# SD_Card.net
KiCad netlist of a schematic drawn in Altium Designer
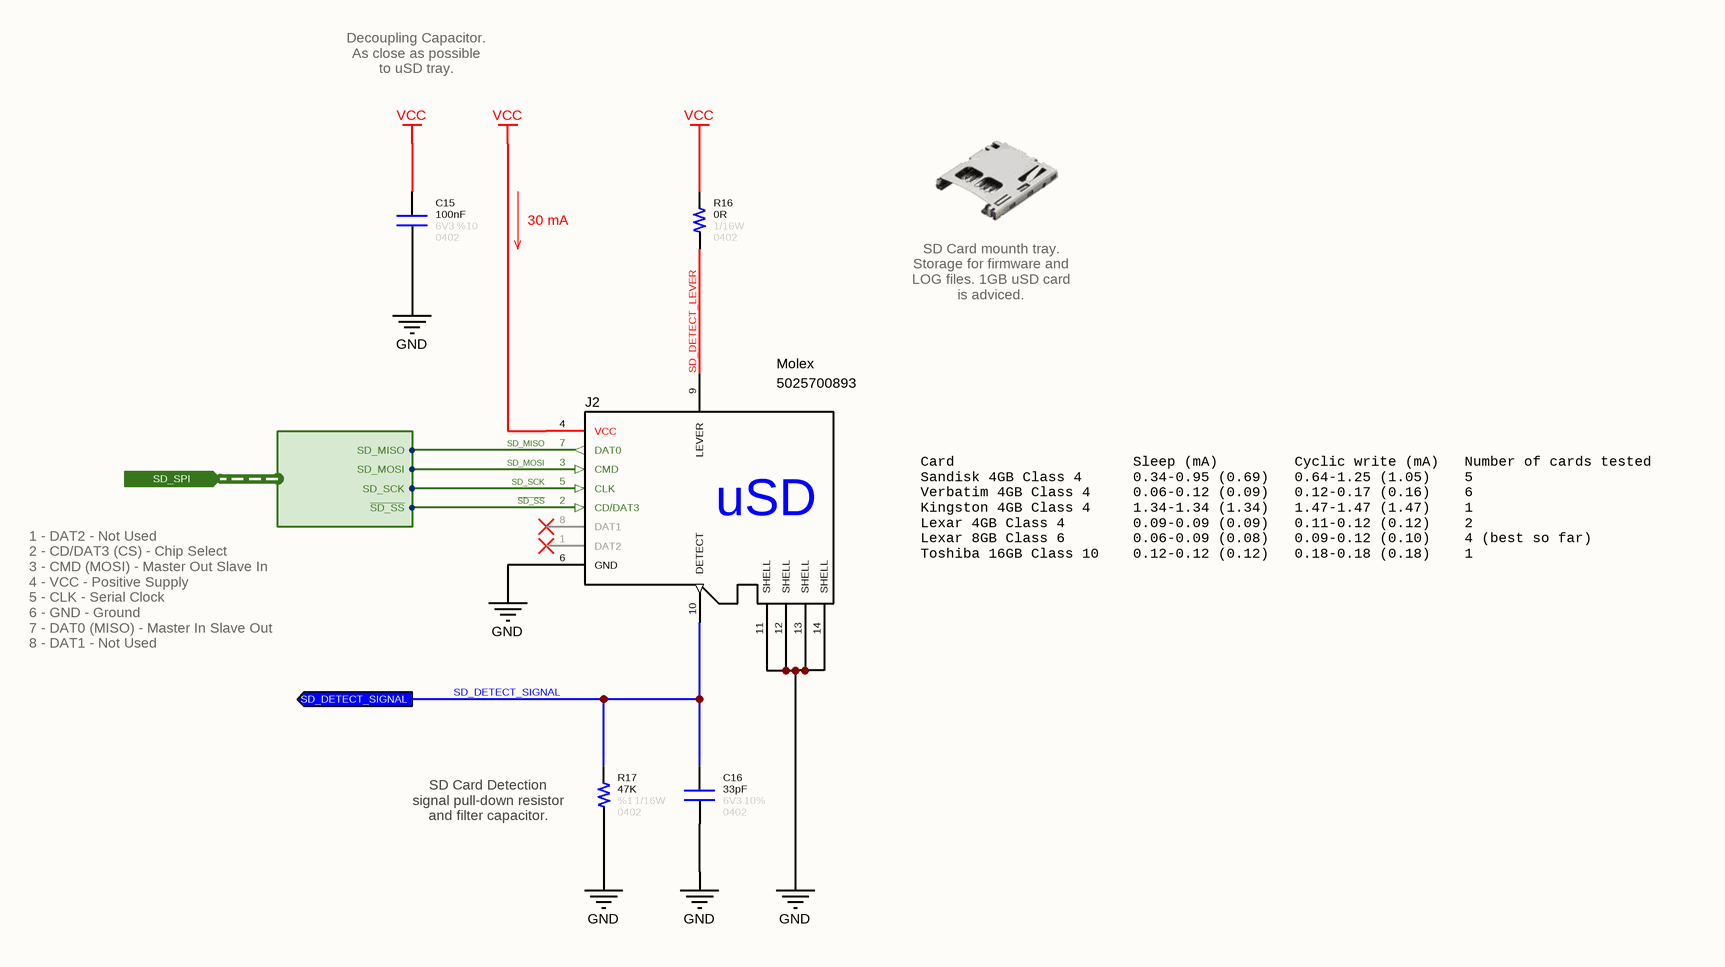
[diagram p0: SD Card.SchDoc]

(export (version "E")
  (design (tool "Eeschema 10.0.6"))
  (components
    (comp (ref "C15")
      (value "100nF")
      (footprint "CAPACITOR_0402")
      (description "Capacitor - 100nF [0402-6V3] (Ceramic)")
      (fields
        (field (name "MANUFACTURER PART NUMBER") "04026D104KAT4A")
        (field (name "TOLERANCE") "%10")
        (field (name "VOLTAGE") "6V3")
        (field (name "CASE") "0402")
        (field (name "Comment") "Capacitor - 100nF [0402] (Ceramic)")
      )
      (libsource (lib "P101DA_Library") (part "Capacitor - 100nF [0402-6V3]"))
    )
    (comp (ref "C16")
      (value "33pF")
      (footprint "CAPACITOR_0402")
      (description "Capacitor - 33pF [0402] (Ceramic)")
      (fields
        (field (name "MANUFACTURER PART NUMBER") "C0402C330J9RACAUTO")
        (field (name "TOLERANCE") "10%")
        (field (name "CASE") "0402")
        (field (name "VOLTAGE") "6V3")
      )
      (libsource (lib "P101DA_Library") (part "Capacitor - 33pF [0402-6V3]"))
    )
    (comp (ref "J2")
      (value "5025700893")
      (footprint "CONNECTOR - SD Card")
      (description "CONN MICRO SD CARD PUSH-PUSH R/A")
      (fields
        (field (name "MANUFACTURER NAME") "Molex")
        (field (name "MANUFACTURER PART NUMBER") "5025700893")
      )
      (libsource (lib "P101DA_Library") (part "Connector - SD Card Slot"))
    )
    (comp (ref "R16")
      (value "0R")
      (footprint "RESISTOR_0402")
      (description "Thick Film Resistors - SMD 1/16 W 0 Ohm")
      (fields
        (field (name "MANUFACTURER PART NUMBER") "CRCW04020000Z0ED")
        (field (name "CASE") "0402")
        (field (name "POWER") "1/16W")
        (field (name "Comment") "0R - 0402 - %1 - 1/16W")
      )
      (libsource (lib "P101DA_Library") (part "Resistor - 0R [0402]"))
    )
    (comp (ref "R17")
      (value "47K")
      (footprint "RESISTOR_0402")
      (description "Thick Film Resistors - SMD 1/16 W 47 KOhm 1%")
      (fields
        (field (name "MANUFACTURER PART NUMBER") "CRCW040247K0FKED")
        (field (name "TOLERANCE") "%1")
        (field (name "CASE") "0402")
        (field (name "POWER") "1/16W")
        (field (name "Comment") "47K - 0402 - %1 - 1/16W")
      )
      (libsource (lib "P101DA_Library") (part "Resistor - 47K [0402]"))
    )
  )
  (nets
    (net (code "2") (name "/SD_DETECT_LEVER") (class "Default")
      (node (ref "J2") (pin "9") (pinfunction "LEVER_9") (pintype "power_in"))
      (node (ref "R16") (pin "1") (pinfunction "1_1") (pintype "passive"))
    )
    (net (code "3") (name "/SD_DETECT_SIGNAL") (class "Default")
      (node (ref "C16") (pin "2") (pinfunction "2_2") (pintype "passive"))
      (node (ref "J2") (pin "10") (pinfunction "DETECT_10") (pintype "output"))
      (node (ref "R17") (pin "2") (pinfunction "2_2") (pintype "passive"))
    )
    (net (code "4") (name "/SD_MISO") (class "Default")
      (node (ref "J2") (pin "7") (pinfunction "DAT0_7") (pintype "output"))
    )
    (net (code "5") (name "/SD_MOSI") (class "Default")
      (node (ref "J2") (pin "3") (pinfunction "CMD_3") (pintype "input"))
    )
    (net (code "6") (name "/SD_SCK") (class "Default")
      (node (ref "J2") (pin "5") (pinfunction "CLK_5") (pintype "input"))
    )
    (net (code "8") (name "/~{SD_SS}") (class "Default")
      (node (ref "J2") (pin "2") (pinfunction "CD/DAT3_2") (pintype "input"))
    )
    (net (code "9") (name "GND") (class "Default")
      (node (ref "C15") (pin "1") (pinfunction "1_1") (pintype "passive"))
      (node (ref "C16") (pin "1") (pinfunction "1_1") (pintype "passive"))
      (node (ref "J2") (pin "11") (pinfunction "SHELL_11") (pintype "power_in"))
      (node (ref "J2") (pin "12") (pinfunction "SHELL_12") (pintype "power_in"))
      (node (ref "J2") (pin "13") (pinfunction "SHELL_13") (pintype "power_in"))
      (node (ref "J2") (pin "14") (pinfunction "SHELL_14") (pintype "power_in"))
      (node (ref "J2") (pin "6") (pinfunction "GND_6") (pintype "power_in"))
      (node (ref "R17") (pin "1") (pinfunction "1_1") (pintype "passive"))
    )
    (net (code "10") (name "VCC") (class "Default")
      (node (ref "C15") (pin "2") (pinfunction "2_2") (pintype "passive"))
      (node (ref "J2") (pin "4") (pinfunction "VCC_4") (pintype "power_in"))
      (node (ref "R16") (pin "2") (pinfunction "2_2") (pintype "passive"))
    )
    (net (code "11") (name "unconnected-(J2-DAT1-Pad8)") (class "Default")
      (node (ref "J2") (pin "8") (pinfunction "DAT1_8") (pintype "passive+no_connect"))
    )
    (net (code "12") (name "unconnected-(J2-DAT2-Pad1)") (class "Default")
      (node (ref "J2") (pin "1") (pinfunction "DAT2_1") (pintype "passive+no_connect"))
    )
  )
)
